# PyNab_Audio.net
KiCad netlist of a schematic drawn in Altium Designer
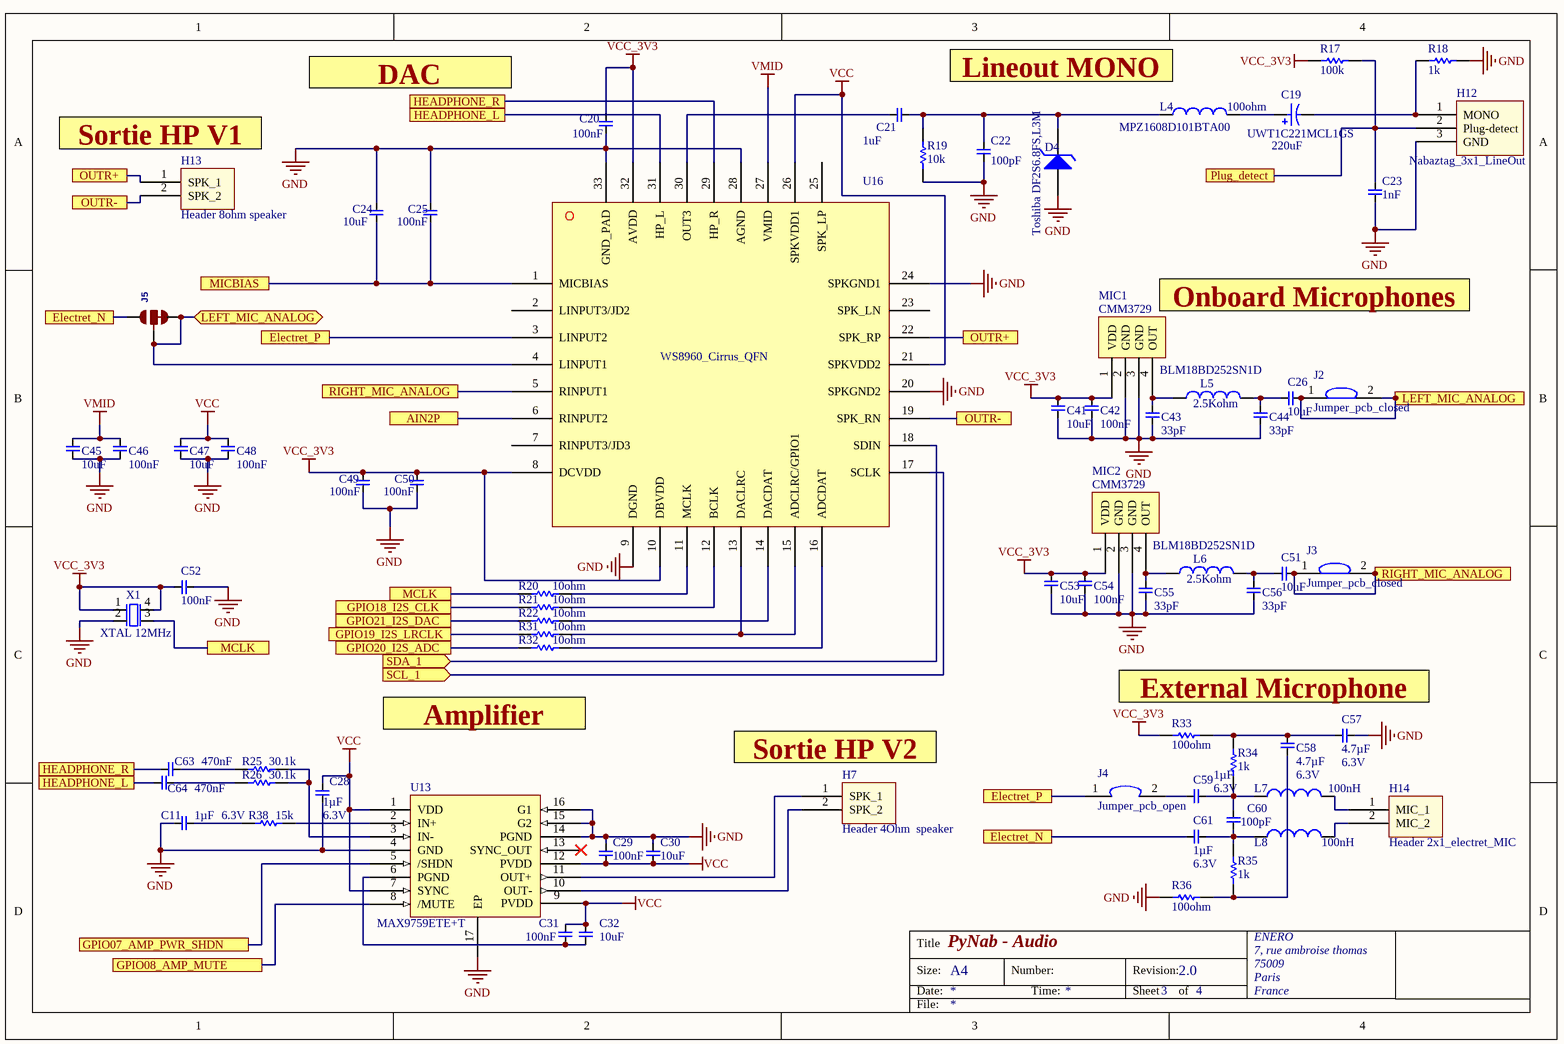
[diagram p0: PyNab_Audio.SchDoc]

(export (version "E")
  (design (tool "Eeschema 10.0.6"))
  (components
    (comp (ref "C11")
      (value "1µF")
      (footprint "CAP0603")
      (description "Non-polarised capacitor")
      (fields (field (name "VOLTAGE") "6.3V"))
      (libsource (lib "PassiveSMT") (part "Capacitor_np"))
    )
    (comp (ref "C19")
      (value "UWT1C221MCL1GS")
      (footprint "CAPAE7066X80M")
      (description "Polarised capacitor")
      (fields (field (name "ALTIUM_VALUE") "220uF"))
      (libsource (lib "PassiveSMT") (part "Capacitor_pol"))
    )
    (comp (ref "C20")
      (value "100nF")
      (footprint "CAP0603")
      (description "Non-polarised capacitor")
      (libsource (lib "PassiveSMT") (part "Capacitor_np"))
    )
    (comp (ref "C21")
      (value "1uF")
      (footprint "CAP0603")
      (description "Non-polarised capacitor")
      (libsource (lib "PassiveSMT") (part "Capacitor_np"))
    )
    (comp (ref "C22")
      (value "100pF")
      (footprint "CAP0603")
      (description "Non-polarised capacitor")
      (libsource (lib "PassiveSMT") (part "Capacitor_np"))
    )
    (comp (ref "C23")
      (value "1nF")
      (footprint "CAP0603")
      (description "Non-polarised capacitor")
      (libsource (lib "PassiveSMT") (part "Capacitor_np"))
    )
    (comp (ref "C24")
      (value "10uF")
      (footprint "CAP0603")
      (description "Non-polarised capacitor")
      (libsource (lib "PassiveSMT") (part "Capacitor_np"))
    )
    (comp (ref "C25")
      (value "100nF")
      (footprint "CAP0603")
      (description "Non-polarised capacitor")
      (libsource (lib "PassiveSMT") (part "Capacitor_np"))
    )
    (comp (ref "C26")
      (value "10uF")
      (footprint "CAP0603")
      (description "Non-polarised capacitor")
      (libsource (lib "PassiveSMT") (part "Capacitor_np"))
    )
    (comp (ref "C28")
      (value "1µF")
      (footprint "CAP0603")
      (description "Non-polarised capacitor")
      (fields (field (name "VOLTAGE") "6.3V"))
      (libsource (lib "PassiveSMT") (part "Capacitor_np"))
    )
    (comp (ref "C29")
      (value "100nF")
      (footprint "CAP0603")
      (description "Non-polarised capacitor")
      (libsource (lib "PassiveSMT") (part "Capacitor_np"))
    )
    (comp (ref "C30")
      (value "10uF")
      (footprint "CAP0603")
      (description "Non-polarised capacitor")
      (libsource (lib "PassiveSMT") (part "Capacitor_np"))
    )
    (comp (ref "C31")
      (value "100nF")
      (footprint "CAP0603")
      (description "Non-polarised capacitor")
      (libsource (lib "PassiveSMT") (part "Capacitor_np"))
    )
    (comp (ref "C32")
      (value "10uF")
      (footprint "CAP0603")
      (description "Non-polarised capacitor")
      (libsource (lib "PassiveSMT") (part "Capacitor_np"))
    )
    (comp (ref "C41")
      (value "10uF")
      (footprint "CAP0603")
      (description "Non-polarised capacitor")
      (libsource (lib "PassiveSMT") (part "Capacitor_np"))
    )
    (comp (ref "C42")
      (value "100nF")
      (footprint "CAP0603")
      (description "Non-polarised capacitor")
      (libsource (lib "PassiveSMT") (part "Capacitor_np"))
    )
    (comp (ref "C43")
      (value "33pF")
      (footprint "CAP0603")
      (description "Non-polarised capacitor")
      (libsource (lib "PassiveSMT") (part "Capacitor_np"))
    )
    (comp (ref "C44")
      (value "33pF")
      (footprint "CAP0603")
      (description "Non-polarised capacitor")
      (libsource (lib "PassiveSMT") (part "Capacitor_np"))
    )
    (comp (ref "C45")
      (value "10uF")
      (footprint "CAP0603")
      (description "Non-polarised capacitor")
      (libsource (lib "PassiveSMT") (part "Capacitor_np"))
    )
    (comp (ref "C46")
      (value "100nF")
      (footprint "CAP0603")
      (description "Non-polarised capacitor")
      (libsource (lib "PassiveSMT") (part "Capacitor_np"))
    )
    (comp (ref "C47")
      (value "10uF")
      (footprint "CAP0603")
      (description "Non-polarised capacitor")
      (libsource (lib "PassiveSMT") (part "Capacitor_np"))
    )
    (comp (ref "C48")
      (value "100nF")
      (footprint "CAP0603")
      (description "Non-polarised capacitor")
      (libsource (lib "PassiveSMT") (part "Capacitor_np"))
    )
    (comp (ref "C49")
      (value "100nF")
      (footprint "CAP0603")
      (description "Non-polarised capacitor")
      (libsource (lib "PassiveSMT") (part "Capacitor_np"))
    )
    (comp (ref "C50")
      (value "100nF")
      (footprint "CAP0603")
      (description "Non-polarised capacitor")
      (libsource (lib "PassiveSMT") (part "Capacitor_np"))
    )
    (comp (ref "C51")
      (value "10uF")
      (footprint "CAP0603")
      (description "Non-polarised capacitor")
      (libsource (lib "PassiveSMT") (part "Capacitor_np"))
    )
    (comp (ref "C52")
      (value "100nF")
      (footprint "CAP0603")
      (description "Non-polarised capacitor")
      (libsource (lib "PassiveSMT") (part "Capacitor_np"))
    )
    (comp (ref "C53")
      (value "10uF")
      (footprint "CAP0603")
      (description "Non-polarised capacitor")
      (libsource (lib "PassiveSMT") (part "Capacitor_np"))
    )
    (comp (ref "C54")
      (value "100nF")
      (footprint "CAP0603")
      (description "Non-polarised capacitor")
      (libsource (lib "PassiveSMT") (part "Capacitor_np"))
    )
    (comp (ref "C55")
      (value "33pF")
      (footprint "CAP0603")
      (description "Non-polarised capacitor")
      (libsource (lib "PassiveSMT") (part "Capacitor_np"))
    )
    (comp (ref "C56")
      (value "33pF")
      (footprint "CAP0603")
      (description "Non-polarised capacitor")
      (libsource (lib "PassiveSMT") (part "Capacitor_np"))
    )
    (comp (ref "C57")
      (value "4.7µF")
      (footprint "CAP0603")
      (description "Non-polarised capacitor")
      (fields (field (name "VOLTAGE") "6.3V"))
      (libsource (lib "PassiveSMT") (part "Capacitor_np"))
    )
    (comp (ref "C58")
      (value "4.7µF")
      (footprint "CAP0603")
      (description "Non-polarised capacitor")
      (fields (field (name "VOLTAGE") "6.3V"))
      (libsource (lib "PassiveSMT") (part "Capacitor_np"))
    )
    (comp (ref "C59")
      (value "1µF")
      (footprint "CAP0603")
      (description "Non-polarised capacitor")
      (fields (field (name "VOLTAGE") "6.3V"))
      (libsource (lib "PassiveSMT") (part "Capacitor_np"))
    )
    (comp (ref "C60")
      (value "100pF")
      (footprint "CAP0603")
      (description "Non-polarised capacitor")
      (fields (field (name "VOLTAGE") "6.3V"))
      (libsource (lib "PassiveSMT") (part "Capacitor_np"))
    )
    (comp (ref "C61")
      (value "1µF")
      (footprint "CAP0603")
      (description "Non-polarised capacitor")
      (fields (field (name "VOLTAGE") "6.3V"))
      (libsource (lib "PassiveSMT") (part "Capacitor_np"))
    )
    (comp (ref "C63")
      (value "470nF")
      (footprint "CAP0603")
      (description "Non-polarised capacitor")
      (libsource (lib "PassiveSMT") (part "Capacitor_np"))
    )
    (comp (ref "C64")
      (value "470nF")
      (footprint "CAP0603")
      (description "Non-polarised capacitor")
      (libsource (lib "PassiveSMT") (part "Capacitor_np"))
    )
    (comp (ref "D4")
      (value "Toshiba DF2S6.8FS,L3M")
      (footprint "Diode SOD-923 DF2S6.8FS")
      (libsource (lib "PassiveSMT") (part "Diode ESD DF2S6.8FS"))
    )
    (comp (ref "H7")
      (value "Header 4Ohm  speaker")
      (footprint "HRD2x1_SPEAKER_Nabaztag")
      (libsource (lib "Enero_HEADERS") (part "Header 2x1_speaker"))
    )
    (comp (ref "H12")
      (value "Nabaztag_3x1_LineOut")
      (footprint "Nabaztag_LineOut")
      (libsource (lib "Enero_HEADERS") (part "Nabaztag_3x1_LineOut"))
    )
    (comp (ref "H13")
      (value "Header 8ohm speaker")
      (footprint "HRD2x1_SPEAKER_Nabaztag")
      (libsource (lib "Enero_HEADERS") (part "Header 2x1_speaker"))
    )
    (comp (ref "H14")
      (value "Header 2x1_electret_MIC")
      (footprint "HRD2x1_MIC_Nabaztag")
      (libsource (lib "Enero_HEADERS") (part "Header 2x1_electret_MIC"))
    )
    (comp (ref "J2")
      (value "Jumper_pcb_closed")
      (footprint "Jumper_pcb_closed 2")
      (libsource (lib "Enero_HEADERS") (part "Jumper_pcb_closed"))
    )
    (comp (ref "J3")
      (value "Jumper_pcb_closed")
      (footprint "Jumper_pcb_closed 2")
      (libsource (lib "Enero_HEADERS") (part "Jumper_pcb_closed"))
    )
    (comp (ref "J4")
      (value "Jumper_pcb_open")
      (footprint "Jumper_pcb open 2")
      (libsource (lib "Enero_HEADERS") (part "Jumper_pcb_open"))
    )
    (comp (ref "J5")
      (value "Normally closed trace jumper (1 of 2 connections)This jumper has a trace between two pads so it's normally closed (NC). The other connection is normally open (NO). Use a razor knife to open the connection. For best results follow the IPC guidelines for cutting traces:Reapply solder to reclose the connection, or to close the NO connection.")
      (footprint "Jumper_pcb_3poles")
      (fields (field (name "LIBRARYNAME") "Sparkfun_jumper"))
      (libsource (lib "Enero_HEADERS") (part "JUMPER-SMT_3_1-NC_TRACE_SILK"))
    )
    (comp (ref "L4")
      (value "MPZ1608D101BTA00")
      (footprint "IND0603")
      (description "Inductor 0603 blm18pg330sn")
      (fields (field (name "ALTIUM_VALUE") "100ohm"))
      (libsource (lib "PassiveSMT") (part "Inductor1"))
    )
    (comp (ref "L5")
      (value "BLM18BD252SN1D")
      (footprint "IND0603")
      (description "Inductor 0603 blm18pg330sn")
      (fields (field (name "ALTIUM_VALUE") "2.5Kohm"))
      (libsource (lib "PassiveSMT") (part "Inductor1"))
    )
    (comp (ref "L6")
      (value "BLM18BD252SN1D")
      (footprint "IND0603")
      (description "Inductor 0603 blm18pg330sn")
      (fields (field (name "ALTIUM_VALUE") "2.5Kohm"))
      (libsource (lib "PassiveSMT") (part "Inductor1"))
    )
    (comp (ref "L7")
      (value "100nH")
      (footprint "IND0603")
      (description "Inductor 0603 MLZ1608DR10DT")
      (fields (field (name "Comment") "MLZ1608DR10DT"))
      (libsource (lib "PassiveSMT") (part "Inductor1"))
    )
    (comp (ref "L8")
      (value "100nH")
      (footprint "IND0603")
      (description "Inductor 0603 MLZ1608DR10DT")
      (fields (field (name "Comment") "MLZ1608DR10DT"))
      (libsource (lib "PassiveSMT") (part "Inductor1"))
    )
    (comp (ref "MIC1")
      (value "CMM3729")
      (footprint "DFN246P295X110-4N")
      (libsource (lib "CMM3729_memsMIC") (part "CMM3729"))
    )
    (comp (ref "MIC2")
      (value "CMM3729")
      (footprint "DFN246P295X110-4N")
      (libsource (lib "CMM3729_memsMIC") (part "CMM3729"))
    )
    (comp (ref "R17")
      (value "100k")
      (footprint "RES0603")
      (description "Resistor")
      (libsource (lib "PassiveSMT") (part "Resistor1"))
    )
    (comp (ref "R18")
      (value "1k")
      (footprint "RES0603")
      (description "Resistor")
      (libsource (lib "PassiveSMT") (part "Resistor1"))
    )
    (comp (ref "R19")
      (value "10k")
      (footprint "RES0603")
      (description "Resistor")
      (libsource (lib "PassiveSMT") (part "Resistor1"))
    )
    (comp (ref "R20")
      (value "10ohm")
      (footprint "RES0603")
      (description "Resistor")
      (libsource (lib "PassiveSMT") (part "Resistor1"))
    )
    (comp (ref "R21")
      (value "10ohm")
      (footprint "RES0603")
      (description "Resistor")
      (libsource (lib "PassiveSMT") (part "Resistor1"))
    )
    (comp (ref "R22")
      (value "10ohm")
      (footprint "RES0603")
      (description "Resistor")
      (libsource (lib "PassiveSMT") (part "Resistor1"))
    )
    (comp (ref "R25")
      (value "30.1k")
      (footprint "RES0603")
      (description "Resistor")
      (libsource (lib "PassiveSMT") (part "Resistor1"))
    )
    (comp (ref "R26")
      (value "30.1k")
      (footprint "RES0603")
      (description "Resistor")
      (libsource (lib "PassiveSMT") (part "Resistor1"))
    )
    (comp (ref "R31")
      (value "10ohm")
      (footprint "RES0603")
      (description "Resistor")
      (libsource (lib "PassiveSMT") (part "Resistor1"))
    )
    (comp (ref "R32")
      (value "10ohm")
      (footprint "RES0603")
      (description "Resistor")
      (libsource (lib "PassiveSMT") (part "Resistor1"))
    )
    (comp (ref "R33")
      (value "100ohm")
      (footprint "RES0603")
      (description "Resistor")
      (libsource (lib "PassiveSMT") (part "Resistor1"))
    )
    (comp (ref "R34")
      (value "1k")
      (footprint "RES0603")
      (description "Resistor")
      (libsource (lib "PassiveSMT") (part "Resistor1"))
    )
    (comp (ref "R35")
      (value "1k")
      (footprint "RES0603")
      (description "Resistor")
      (libsource (lib "PassiveSMT") (part "Resistor1"))
    )
    (comp (ref "R36")
      (value "100ohm")
      (footprint "RES0603")
      (description "Resistor")
      (libsource (lib "PassiveSMT") (part "Resistor1"))
    )
    (comp (ref "R38")
      (value "15k")
      (footprint "RES0603")
      (description "Resistor")
      (libsource (lib "PassiveSMT") (part "Resistor1"))
    )
    (comp (ref "U13")
      (value "MAX9759ETE+T")
      (footprint "MAX9759ETE+T")
      (libsource (lib "MAX9759") (part "MAX9759ETE+T"))
    )
    (comp (ref "U16")
      (value "WS8960_Cirrus_QFN")
      (footprint "QFN50P500X500X100_HS-33N")
      (libsource (lib "WM8960") (part "WS8960_Cirrus_QFN"))
    )
    (comp (ref "X1")
      (value "XTAL 12MHz")
      (footprint "XTAL_2025_4Pin ECS-2520S33-120-FN-TR")
      (libsource (lib "PassiveSMT") (part "XTAL_2025_4pin"))
    )
  )
  (nets
    (net (code "1") (name "/AIN2P") (class "Default")
      (node (ref "U16") (pin "6") (pinfunction "RINPUT2_6") (pintype "passive"))
    )
    (net (code "2") (name "/Electret_N") (class "Default")
      (node (ref "C61") (pin "2") (pinfunction "2_2") (pintype "passive"))
      (node (ref "J5") (pin "1") (pinfunction "1_1") (pintype "passive"))
    )
    (net (code "3") (name "/Electret_P") (class "Default")
      (node (ref "J4") (pin "1") (pinfunction "1_1") (pintype "passive"))
      (node (ref "U16") (pin "3") (pinfunction "LINPUT2_3") (pintype "passive"))
    )
    (net (code "4") (name "/GPIO07_AMP_PWR_SHDN") (class "Default")
      (node (ref "U13") (pin "5") (pinfunction "/SHDN_5") (pintype "input"))
    )
    (net (code "5") (name "/GPIO08_AMP_MUTE") (class "Default")
      (node (ref "U13") (pin "8") (pinfunction "/MUTE_8") (pintype "input"))
    )
    (net (code "6") (name "/GPIO18_I2S_CLK") (class "Default")
      (node (ref "R21") (pin "2") (pinfunction "2_2") (pintype "passive"))
    )
    (net (code "7") (name "/GPIO19_I2S_LRCLK") (class "Default")
      (node (ref "R31") (pin "2") (pinfunction "2_2") (pintype "passive"))
    )
    (net (code "8") (name "/GPIO20_I2S_ADC") (class "Default")
      (node (ref "R32") (pin "2") (pinfunction "2_2") (pintype "passive"))
    )
    (net (code "9") (name "/GPIO21_I2S_DAC") (class "Default")
      (node (ref "R22") (pin "2") (pinfunction "2_2") (pintype "passive"))
    )
    (net (code "10") (name "/HEADPHONE_L") (class "Default")
      (node (ref "C64") (pin "2") (pinfunction "2_2") (pintype "passive"))
      (node (ref "U16") (pin "31") (pinfunction "HP_L_31") (pintype "passive"))
    )
    (net (code "11") (name "/HEADPHONE_R") (class "Default")
      (node (ref "C63") (pin "2") (pinfunction "2_2") (pintype "passive"))
      (node (ref "U16") (pin "29") (pinfunction "HP_R_29") (pintype "passive"))
    )
    (net (code "12") (name "/LEFT_MIC_ANALOG") (class "Default")
      (node (ref "C26") (pin "2") (pinfunction "2_2") (pintype "passive"))
      (node (ref "J2") (pin "1") (pinfunction "1_1") (pintype "passive"))
      (node (ref "J2") (pin "2") (pinfunction "2_2") (pintype "passive"))
      (node (ref "J5") (pin "2") (pinfunction "2_2") (pintype "passive"))
      (node (ref "J5") (pin "3") (pinfunction "3_3") (pintype "passive"))
      (node (ref "U16") (pin "4") (pinfunction "LINPUT1_4") (pintype "passive"))
    )
    (net (code "13") (name "/MCLK") (class "Default")
      (node (ref "R20") (pin "2") (pinfunction "2_2") (pintype "passive"))
      (node (ref "X1") (pin "3") (pinfunction "OUT_3") (pintype "passive"))
    )
    (net (code "14") (name "/MICBIAS") (class "Default")
      (node (ref "C24") (pin "1") (pinfunction "1_1") (pintype "passive"))
      (node (ref "C25") (pin "1") (pinfunction "1_1") (pintype "passive"))
      (node (ref "U16") (pin "1") (pinfunction "MICBIAS_1") (pintype "passive"))
    )
    (net (code "15") (name "/OUTR+") (class "Default")
      (node (ref "H13") (pin "1") (pinfunction "SPK_1_1") (pintype "passive"))
      (node (ref "U16") (pin "22") (pinfunction "SPK_RP_22") (pintype "passive"))
    )
    (net (code "16") (name "/OUTR-") (class "Default")
      (node (ref "H13") (pin "2") (pinfunction "SPK_2_2") (pintype "passive"))
      (node (ref "U16") (pin "19") (pinfunction "SPK_RN_19") (pintype "passive"))
    )
    (net (code "17") (name "/Plug_detect") (class "Default")
      (node (ref "C23") (pin "2") (pinfunction "2_2") (pintype "passive"))
      (node (ref "H12") (pin "2") (pinfunction "Plug-detect_2") (pintype "passive"))
      (node (ref "R17") (pin "1") (pinfunction "1_1") (pintype "passive"))
    )
    (net (code "18") (name "/RIGHT_MIC_ANALOG") (class "Default")
      (node (ref "C51") (pin "2") (pinfunction "2_2") (pintype "passive"))
      (node (ref "J3") (pin "1") (pinfunction "1_1") (pintype "passive"))
      (node (ref "J3") (pin "2") (pinfunction "2_2") (pintype "passive"))
      (node (ref "U16") (pin "5") (pinfunction "RINPUT1_5") (pintype "passive"))
    )
    (net (code "19") (name "/SCL_1") (class "Default")
      (node (ref "U16") (pin "17") (pinfunction "SCLK_17") (pintype "passive"))
    )
    (net (code "20") (name "/SDA_1") (class "Default")
      (node (ref "U16") (pin "18") (pinfunction "SDIN_18") (pintype "passive"))
    )
    (net (code "21") (name "GND") (class "Default")
      (node (ref "C11") (pin "2") (pinfunction "2_2") (pintype "passive"))
      (node (ref "C20") (pin "1") (pinfunction "1_1") (pintype "passive"))
      (node (ref "C22") (pin "1") (pinfunction "1_1") (pintype "passive"))
      (node (ref "C23") (pin "1") (pinfunction "1_1") (pintype "passive"))
      (node (ref "C24") (pin "2") (pinfunction "2_2") (pintype "passive"))
      (node (ref "C25") (pin "2") (pinfunction "2_2") (pintype "passive"))
      (node (ref "C28") (pin "2") (pinfunction "2_2") (pintype "passive"))
      (node (ref "C29") (pin "2") (pinfunction "2_2") (pintype "passive"))
      (node (ref "C30") (pin "1") (pinfunction "1_1") (pintype "passive"))
      (node (ref "C41") (pin "2") (pinfunction "2_2") (pintype "passive"))
      (node (ref "C42") (pin "1") (pinfunction "1_1") (pintype "passive"))
      (node (ref "C43") (pin "1") (pinfunction "1_1") (pintype "passive"))
      (node (ref "C44") (pin "1") (pinfunction "1_1") (pintype "passive"))
      (node (ref "C45") (pin "2") (pinfunction "2_2") (pintype "passive"))
      (node (ref "C46") (pin "1") (pinfunction "1_1") (pintype "passive"))
      (node (ref "C47") (pin "2") (pinfunction "2_2") (pintype "passive"))
      (node (ref "C48") (pin "1") (pinfunction "1_1") (pintype "passive"))
      (node (ref "C49") (pin "1") (pinfunction "1_1") (pintype "passive"))
      (node (ref "C50") (pin "1") (pinfunction "1_1") (pintype "passive"))
      (node (ref "C52") (pin "1") (pinfunction "1_1") (pintype "passive"))
      (node (ref "C53") (pin "2") (pinfunction "2_2") (pintype "passive"))
      (node (ref "C54") (pin "1") (pinfunction "1_1") (pintype "passive"))
      (node (ref "C55") (pin "1") (pinfunction "1_1") (pintype "passive"))
      (node (ref "C56") (pin "1") (pinfunction "1_1") (pintype "passive"))
      (node (ref "C57") (pin "2") (pinfunction "2_2") (pintype "passive"))
      (node (ref "D4") (pin "2") (pinfunction "A_2") (pintype "passive"))
      (node (ref "H12") (pin "3") (pinfunction "GND_3") (pintype "passive"))
      (node (ref "MIC1") (pin "2") (pinfunction "GND_2") (pintype "passive"))
      (node (ref "MIC1") (pin "3") (pinfunction "GND_3") (pintype "passive"))
      (node (ref "MIC2") (pin "2") (pinfunction "GND_2") (pintype "passive"))
      (node (ref "MIC2") (pin "3") (pinfunction "GND_3") (pintype "passive"))
      (node (ref "R18") (pin "1") (pinfunction "1_1") (pintype "passive"))
      (node (ref "R19") (pin "1") (pinfunction "1_1") (pintype "passive"))
      (node (ref "R36") (pin "2") (pinfunction "2_2") (pintype "passive"))
      (node (ref "U13") (pin "14") (pinfunction "PGND_14") (pintype "power_in"))
      (node (ref "U13") (pin "15") (pinfunction "G2_15") (pintype "input"))
      (node (ref "U13") (pin "16") (pinfunction "G1_16") (pintype "input"))
      (node (ref "U13") (pin "17") (pinfunction "EP_17") (pintype "power_in"))
      (node (ref "U13") (pin "4") (pinfunction "GND_4") (pintype "power_in"))
      (node (ref "U16") (pin "20") (pinfunction "SPKGND2_20") (pintype "passive"))
      (node (ref "U16") (pin "24") (pinfunction "SPKGND1_24") (pintype "passive"))
      (node (ref "U16") (pin "28") (pinfunction "AGND_28") (pintype "passive"))
      (node (ref "U16") (pin "33") (pinfunction "GND_PAD_33") (pintype "passive"))
      (node (ref "U16") (pin "9") (pinfunction "DGND_9") (pintype "passive"))
      (node (ref "X1") (pin "2") (pinfunction "GND_2") (pintype "passive"))
    )
    (net (code "22") (name "Net-(C11-Pad1)") (class "Default")
      (node (ref "C11") (pin "1") (pinfunction "1_1") (pintype "passive"))
      (node (ref "R38") (pin "2") (pinfunction "2_2") (pintype "passive"))
    )
    (net (code "23") (name "Net-(C19-A)") (class "Default")
      (node (ref "C19") (pin "2") (pinfunction "A_2") (pintype "passive"))
      (node (ref "L4") (pin "1") (pinfunction "1_1") (pintype "passive"))
    )
    (net (code "24") (name "Net-(C19-K)") (class "Default")
      (node (ref "C19") (pin "1") (pinfunction "K_1") (pintype "passive"))
      (node (ref "H12") (pin "1") (pinfunction "MONO_1") (pintype "passive"))
      (node (ref "R18") (pin "2") (pinfunction "2_2") (pintype "passive"))
    )
    (net (code "25") (name "Net-(C26-Pad1)") (class "Default")
      (node (ref "C26") (pin "1") (pinfunction "1_1") (pintype "passive"))
      (node (ref "C44") (pin "2") (pinfunction "2_2") (pintype "passive"))
      (node (ref "L5") (pin "1") (pinfunction "1_1") (pintype "passive"))
    )
    (net (code "26") (name "Net-(C31-Pad1)") (class "Default")
      (node (ref "C31") (pin "1") (pinfunction "1_1") (pintype "passive"))
      (node (ref "C32") (pin "2") (pinfunction "2_2") (pintype "passive"))
      (node (ref "U13") (pin "6") (pinfunction "PGND_6") (pintype "power_in"))
    )
    (net (code "27") (name "Net-(C51-Pad1)") (class "Default")
      (node (ref "C51") (pin "1") (pinfunction "1_1") (pintype "passive"))
      (node (ref "C56") (pin "2") (pinfunction "2_2") (pintype "passive"))
      (node (ref "L6") (pin "1") (pinfunction "1_1") (pintype "passive"))
    )
    (net (code "28") (name "Net-(C57-Pad1)") (class "Default")
      (node (ref "C57") (pin "1") (pinfunction "1_1") (pintype "passive"))
      (node (ref "C58") (pin "1") (pinfunction "1_1") (pintype "passive"))
      (node (ref "R33") (pin "1") (pinfunction "1_1") (pintype "passive"))
      (node (ref "R34") (pin "2") (pinfunction "2_2") (pintype "passive"))
    )
    (net (code "29") (name "Net-(C58-Pad2)") (class "Default")
      (node (ref "C58") (pin "2") (pinfunction "2_2") (pintype "passive"))
      (node (ref "R35") (pin "1") (pinfunction "1_1") (pintype "passive"))
      (node (ref "R36") (pin "1") (pinfunction "1_1") (pintype "passive"))
    )
    (net (code "30") (name "Net-(C59-Pad1)") (class "Default")
      (node (ref "C59") (pin "1") (pinfunction "1_1") (pintype "passive"))
      (node (ref "C60") (pin "1") (pinfunction "1_1") (pintype "passive"))
      (node (ref "L7") (pin "2") (pinfunction "2_2") (pintype "passive"))
      (node (ref "R34") (pin "1") (pinfunction "1_1") (pintype "passive"))
    )
    (net (code "31") (name "Net-(C59-Pad2)") (class "Default")
      (node (ref "C59") (pin "2") (pinfunction "2_2") (pintype "passive"))
      (node (ref "J4") (pin "2") (pinfunction "2_2") (pintype "passive"))
    )
    (net (code "32") (name "Net-(C60-Pad2)") (class "Default")
      (node (ref "C60") (pin "2") (pinfunction "2_2") (pintype "passive"))
      (node (ref "C61") (pin "1") (pinfunction "1_1") (pintype "passive"))
      (node (ref "L8") (pin "2") (pinfunction "2_2") (pintype "passive"))
      (node (ref "R35") (pin "2") (pinfunction "2_2") (pintype "passive"))
    )
    (net (code "33") (name "Net-(C63-Pad1)") (class "Default")
      (node (ref "C63") (pin "1") (pinfunction "1_1") (pintype "passive"))
      (node (ref "R25") (pin "2") (pinfunction "2_2") (pintype "passive"))
    )
    (net (code "34") (name "Net-(C64-Pad1)") (class "Default")
      (node (ref "C64") (pin "1") (pinfunction "1_1") (pintype "passive"))
      (node (ref "R26") (pin "2") (pinfunction "2_2") (pintype "passive"))
    )
    (net (code "35") (name "Net-(D4-K)") (class "Default")
      (node (ref "C21") (pin "2") (pinfunction "2_2") (pintype "passive"))
      (node (ref "C22") (pin "2") (pinfunction "2_2") (pintype "passive"))
      (node (ref "D4") (pin "1") (pinfunction "K_1") (pintype "passive"))
      (node (ref "L4") (pin "2") (pinfunction "2_2") (pintype "passive"))
      (node (ref "R19") (pin "2") (pinfunction "2_2") (pintype "passive"))
    )
    (net (code "36") (name "Net-(H7-SPK_1)") (class "Default")
      (node (ref "H7") (pin "1") (pinfunction "SPK_1_1") (pintype "passive"))
      (node (ref "U13") (pin "11") (pinfunction "OUT+_11") (pintype "output"))
    )
    (net (code "37") (name "Net-(H7-SPK_2)") (class "Default")
      (node (ref "H7") (pin "2") (pinfunction "SPK_2_2") (pintype "passive"))
      (node (ref "U13") (pin "10") (pinfunction "OUT-_10") (pintype "output"))
    )
    (net (code "38") (name "Net-(H14-MIC_1)") (class "Default")
      (node (ref "H14") (pin "1") (pinfunction "MIC_1_1") (pintype "passive"))
      (node (ref "L7") (pin "1") (pinfunction "1_1") (pintype "passive"))
    )
    (net (code "39") (name "Net-(H14-MIC_2)") (class "Default")
      (node (ref "H14") (pin "2") (pinfunction "MIC_2_2") (pintype "passive"))
      (node (ref "L8") (pin "1") (pinfunction "1_1") (pintype "passive"))
    )
    (net (code "40") (name "Net-(MIC1-OUT)") (class "Default")
      (node (ref "C43") (pin "2") (pinfunction "2_2") (pintype "passive"))
      (node (ref "L5") (pin "2") (pinfunction "2_2") (pintype "passive"))
      (node (ref "MIC1") (pin "4") (pinfunction "OUT_4") (pintype "passive"))
    )
    (net (code "41") (name "Net-(MIC2-OUT)") (class "Default")
      (node (ref "C55") (pin "2") (pinfunction "2_2") (pintype "passive"))
      (node (ref "L6") (pin "2") (pinfunction "2_2") (pintype "passive"))
      (node (ref "MIC2") (pin "4") (pinfunction "OUT_4") (pintype "passive"))
    )
    (net (code "42") (name "Net-(U13-IN+)") (class "Default")
      (node (ref "R38") (pin "1") (pinfunction "1_1") (pintype "passive"))
      (node (ref "U13") (pin "2") (pinfunction "IN+_2") (pintype "input"))
    )
    (net (code "43") (name "Net-(U13-IN-)") (class "Default")
      (node (ref "R25") (pin "1") (pinfunction "1_1") (pintype "passive"))
      (node (ref "R26") (pin "1") (pinfunction "1_1") (pintype "passive"))
      (node (ref "U13") (pin "3") (pinfunction "IN-_3") (pintype "input"))
    )
    (net (code "44") (name "Net-(U16-ADCDAT)") (class "Default")
      (node (ref "R32") (pin "1") (pinfunction "1_1") (pintype "passive"))
      (node (ref "U16") (pin "16") (pinfunction "ADCDAT_16") (pintype "passive"))
    )
    (net (code "45") (name "Net-(U16-ADCLRC{slash}GPIO1)") (class "Default")
      (node (ref "R31") (pin "1") (pinfunction "1_1") (pintype "passive"))
      (node (ref "U16") (pin "13") (pinfunction "DACLRC_13") (pintype "passive"))
      (node (ref "U16") (pin "15") (pinfunction "ADCLRC/GPIO1_15") (pintype "passive"))
    )
    (net (code "46") (name "Net-(U16-BCLK)") (class "Default")
      (node (ref "R21") (pin "1") (pinfunction "1_1") (pintype "passive"))
      (node (ref "U16") (pin "12") (pinfunction "BCLK_12") (pintype "passive"))
    )
    (net (code "47") (name "Net-(U16-DACDAT)") (class "Default")
      (node (ref "R22") (pin "1") (pinfunction "1_1") (pintype "passive"))
      (node (ref "U16") (pin "14") (pinfunction "DACDAT_14") (pintype "passive"))
    )
    (net (code "48") (name "Net-(U16-MCLK)") (class "Default")
      (node (ref "R20") (pin "1") (pinfunction "1_1") (pintype "passive"))
      (node (ref "U16") (pin "11") (pinfunction "MCLK_11") (pintype "passive"))
    )
    (net (code "49") (name "Net-(U16-OUT3)") (class "Default")
      (node (ref "C21") (pin "1") (pinfunction "1_1") (pintype "passive"))
      (node (ref "U16") (pin "30") (pinfunction "OUT3_30") (pintype "passive"))
    )
    (net (code "50") (name "VCC") (class "Default")
      (node (ref "C28") (pin "1") (pinfunction "1_1") (pintype "passive"))
      (node (ref "C29") (pin "1") (pinfunction "1_1") (pintype "passive"))
      (node (ref "C30") (pin "2") (pinfunction "2_2") (pintype "passive"))
      (node (ref "C31") (pin "2") (pinfunction "2_2") (pintype "passive"))
      (node (ref "C32") (pin "1") (pinfunction "1_1") (pintype "passive"))
      (node (ref "C47") (pin "1") (pinfunction "1_1") (pintype "passive"))
      (node (ref "C48") (pin "2") (pinfunction "2_2") (pintype "passive"))
      (node (ref "U13") (pin "1") (pinfunction "VDD_1") (pintype "power_in"))
      (node (ref "U13") (pin "12") (pinfunction "PVDD_12") (pintype "power_in"))
      (node (ref "U13") (pin "7") (pinfunction "SYNC_7") (pintype "input"))
      (node (ref "U13") (pin "9") (pinfunction "PVDD_9") (pintype "power_in"))
      (node (ref "U16") (pin "21") (pinfunction "SPKVDD2_21") (pintype "passive"))
      (node (ref "U16") (pin "26") (pinfunction "SPKVDD1_26") (pintype "passive"))
    )
    (net (code "51") (name "VCC_3V3") (class "Default")
      (node (ref "C20") (pin "2") (pinfunction "2_2") (pintype "passive"))
      (node (ref "C41") (pin "1") (pinfunction "1_1") (pintype "passive"))
      (node (ref "C42") (pin "2") (pinfunction "2_2") (pintype "passive"))
      (node (ref "C49") (pin "2") (pinfunction "2_2") (pintype "passive"))
      (node (ref "C50") (pin "2") (pinfunction "2_2") (pintype "passive"))
      (node (ref "C52") (pin "2") (pinfunction "2_2") (pintype "passive"))
      (node (ref "C53") (pin "1") (pinfunction "1_1") (pintype "passive"))
      (node (ref "C54") (pin "2") (pinfunction "2_2") (pintype "passive"))
      (node (ref "MIC1") (pin "1") (pinfunction "VDD_1") (pintype "passive"))
      (node (ref "MIC2") (pin "1") (pinfunction "VDD_1") (pintype "passive"))
      (node (ref "R17") (pin "2") (pinfunction "2_2") (pintype "passive"))
      (node (ref "R33") (pin "2") (pinfunction "2_2") (pintype "passive"))
      (node (ref "U16") (pin "10") (pinfunction "DBVDD_10") (pintype "passive"))
      (node (ref "U16") (pin "32") (pinfunction "AVDD_32") (pintype "passive"))
      (node (ref "U16") (pin "8") (pinfunction "DCVDD_8") (pintype "passive"))
      (node (ref "X1") (pin "1") (pinfunction "EN_1") (pintype "passive"))
      (node (ref "X1") (pin "4") (pinfunction "VDD_4") (pintype "passive"))
    )
    (net (code "52") (name "VMID") (class "Default")
      (node (ref "C45") (pin "1") (pinfunction "1_1") (pintype "passive"))
      (node (ref "C46") (pin "2") (pinfunction "2_2") (pintype "passive"))
      (node (ref "U16") (pin "27") (pinfunction "VMID_27") (pintype "passive"))
    )
    (net (code "53") (name "unconnected-(U13-SYNC_OUT-Pad13)") (class "Default")
      (node (ref "U13") (pin "13") (pinfunction "SYNC_OUT_13") (pintype "input+no_connect"))
    )
    (net (code "54") (name "unconnected-(U16-LINPUT3{slash}JD2-Pad2)") (class "Default")
      (node (ref "U16") (pin "2") (pinfunction "LINPUT3/JD2_2") (pintype "passive"))
    )
    (net (code "55") (name "unconnected-(U16-RINPUT3{slash}JD3-Pad7)") (class "Default")
      (node (ref "U16") (pin "7") (pinfunction "RINPUT3/JD3_7") (pintype "passive"))
    )
    (net (code "56") (name "unconnected-(U16-SPK_LN-Pad23)") (class "Default")
      (node (ref "U16") (pin "23") (pinfunction "SPK_LN_23") (pintype "passive"))
    )
    (net (code "57") (name "unconnected-(U16-SPK_LP-Pad25)") (class "Default")
      (node (ref "U16") (pin "25") (pinfunction "SPK_LP_25") (pintype "passive"))
    )
  )
)
